# FPGA_Supply_Pins.net
KiCad netlist of a schematic drawn in Altium Designer
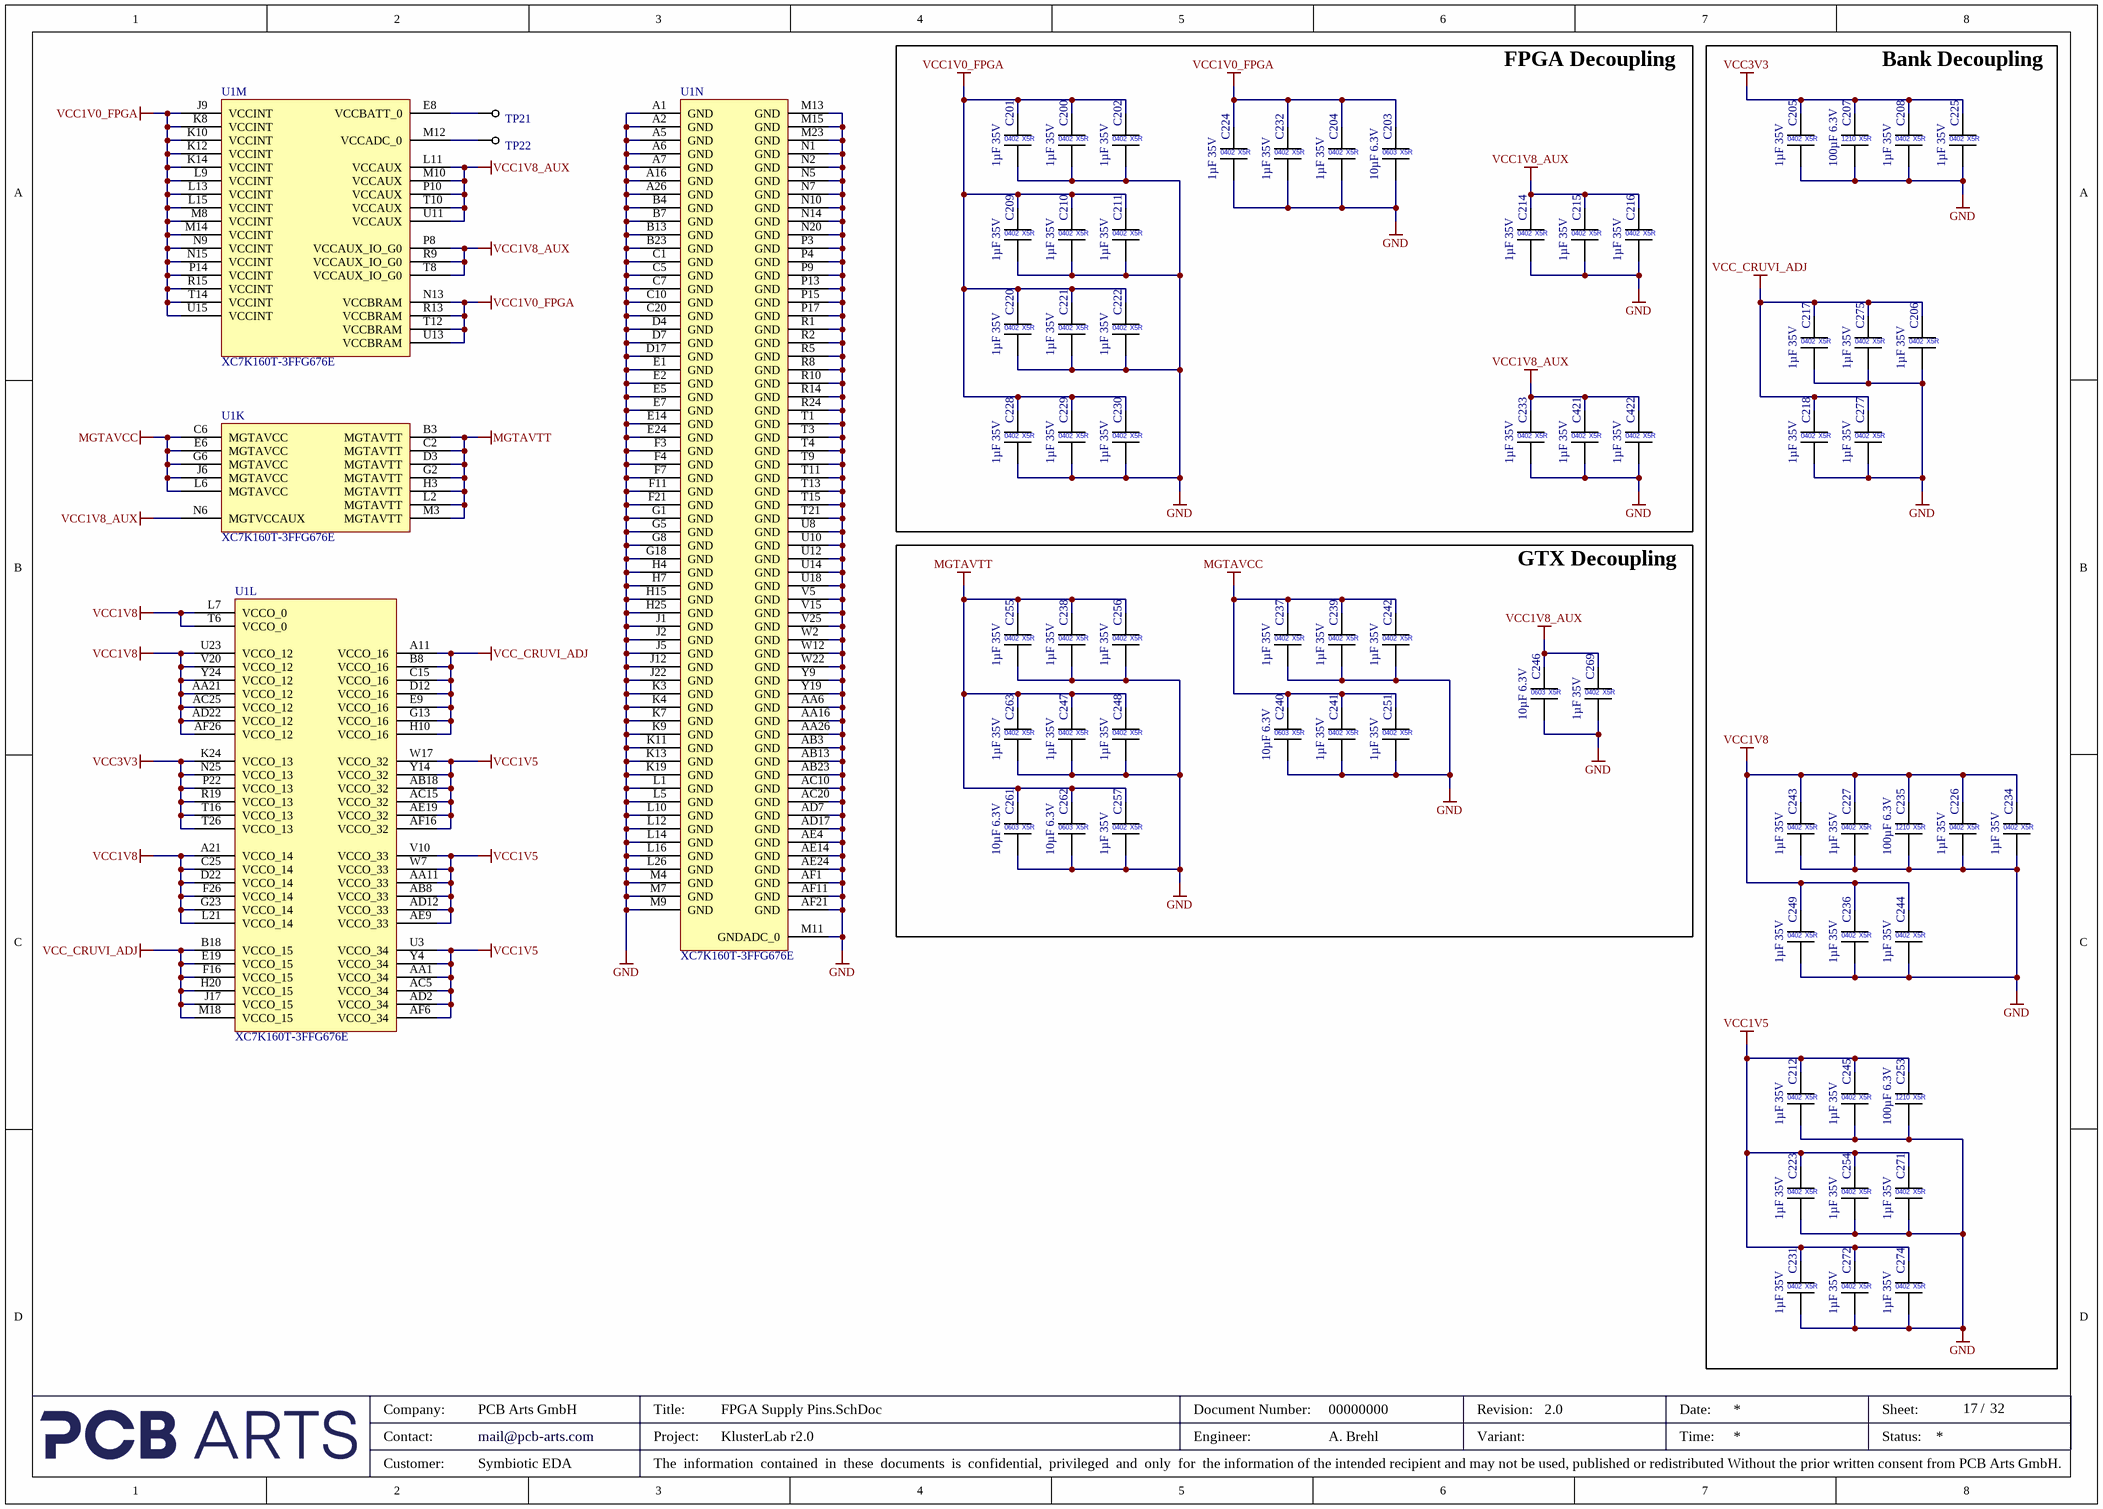
[diagram p0: FPGA Supply Pins.SchDoc]

(export (version "E")
  (design (tool "Eeschema 10.0.6"))
  (components
    (comp (ref "C200")
      (value "1µF 35V")
      (footprint "Cap:CAP_0402_L")
      (description "Multilayer Ceramic Capacitors MLCC - SMD/SMT 0402 35VDC")
      (libsource (lib "Cap") (part "CAP_0402_1µF_35V"))
    )
    (comp (ref "C201")
      (value "1µF 35V")
      (footprint "Cap:CAP_0402_L")
      (description "Multilayer Ceramic Capacitors MLCC - SMD/SMT 0402 35VDC")
      (libsource (lib "Cap") (part "CAP_0402_1µF_35V"))
    )
    (comp (ref "C202")
      (value "1µF 35V")
      (footprint "Cap:CAP_0402_L")
      (description "Multilayer Ceramic Capacitors MLCC - SMD/SMT 0402 35VDC")
      (libsource (lib "Cap") (part "CAP_0402_1µF_35V"))
    )
    (comp (ref "C203")
      (value "10µF 6.3V")
      (footprint "Cap:CAP_0603_L")
      (description "Multilayer Ceramic Capacitors MLCC - SMD/SMT 0603 6.3VDC")
      (libsource (lib "Cap") (part "CAP_0603_10µF_6.3V"))
    )
    (comp (ref "C204")
      (value "1µF 35V")
      (footprint "Cap:CAP_0402_L")
      (description "Multilayer Ceramic Capacitors MLCC - SMD/SMT 0402 35VDC")
      (libsource (lib "Cap") (part "CAP_0402_1µF_35V"))
    )
    (comp (ref "C205")
      (value "1µF 35V")
      (footprint "Cap:CAP_0402_L")
      (description "Multilayer Ceramic Capacitors MLCC - SMD/SMT 0402 35VDC")
      (libsource (lib "Cap") (part "CAP_0402_1µF_35V"))
    )
    (comp (ref "C206")
      (value "1µF 35V")
      (footprint "Cap:CAP_0402_L")
      (description "Multilayer Ceramic Capacitors MLCC - SMD/SMT 0402 35VDC")
      (libsource (lib "Cap") (part "CAP_0402_1µF_35V"))
    )
    (comp (ref "C207")
      (value "100µF 6.3V")
      (footprint "Cap:CAP_1210")
      (description "Multilayer Ceramic Capacitors MLCC - SMD/SMT 1210 6.3VDC")
      (libsource (lib "Cap") (part "CAP_1210_100µF_6.3V"))
    )
    (comp (ref "C208")
      (value "1µF 35V")
      (footprint "Cap:CAP_0402_L")
      (description "Multilayer Ceramic Capacitors MLCC - SMD/SMT 0402 35VDC")
      (libsource (lib "Cap") (part "CAP_0402_1µF_35V"))
    )
    (comp (ref "C209")
      (value "1µF 35V")
      (footprint "Cap:CAP_0402_L")
      (description "Multilayer Ceramic Capacitors MLCC - SMD/SMT 0402 35VDC")
      (libsource (lib "Cap") (part "CAP_0402_1µF_35V"))
    )
    (comp (ref "C210")
      (value "1µF 35V")
      (footprint "Cap:CAP_0402_L")
      (description "Multilayer Ceramic Capacitors MLCC - SMD/SMT 0402 35VDC")
      (libsource (lib "Cap") (part "CAP_0402_1µF_35V"))
    )
    (comp (ref "C211")
      (value "1µF 35V")
      (footprint "Cap:CAP_0402_L")
      (description "Multilayer Ceramic Capacitors MLCC - SMD/SMT 0402 35VDC")
      (libsource (lib "Cap") (part "CAP_0402_1µF_35V"))
    )
    (comp (ref "C212")
      (value "1µF 35V")
      (footprint "Cap:CAP_0402_L")
      (description "Multilayer Ceramic Capacitors MLCC - SMD/SMT 0402 35VDC")
      (libsource (lib "Cap") (part "CAP_0402_1µF_35V"))
    )
    (comp (ref "C214")
      (value "1µF 35V")
      (footprint "Cap:CAP_0402_L")
      (description "Multilayer Ceramic Capacitors MLCC - SMD/SMT 0402 35VDC")
      (libsource (lib "Cap") (part "CAP_0402_1µF_35V"))
    )
    (comp (ref "C215")
      (value "1µF 35V")
      (footprint "Cap:CAP_0402_L")
      (description "Multilayer Ceramic Capacitors MLCC - SMD/SMT 0402 35VDC")
      (libsource (lib "Cap") (part "CAP_0402_1µF_35V"))
    )
    (comp (ref "C216")
      (value "1µF 35V")
      (footprint "Cap:CAP_0402_L")
      (description "Multilayer Ceramic Capacitors MLCC - SMD/SMT 0402 35VDC")
      (libsource (lib "Cap") (part "CAP_0402_1µF_35V"))
    )
    (comp (ref "C217")
      (value "1µF 35V")
      (footprint "Cap:CAP_0402_L")
      (description "Multilayer Ceramic Capacitors MLCC - SMD/SMT 0402 35VDC")
      (libsource (lib "Cap") (part "CAP_0402_1µF_35V"))
    )
    (comp (ref "C218")
      (value "1µF 35V")
      (footprint "Cap:CAP_0402_L")
      (description "Multilayer Ceramic Capacitors MLCC - SMD/SMT 0402 35VDC")
      (libsource (lib "Cap") (part "CAP_0402_1µF_35V"))
    )
    (comp (ref "C220")
      (value "1µF 35V")
      (footprint "Cap:CAP_0402_L")
      (description "Multilayer Ceramic Capacitors MLCC - SMD/SMT 0402 35VDC")
      (libsource (lib "Cap") (part "CAP_0402_1µF_35V"))
    )
    (comp (ref "C221")
      (value "1µF 35V")
      (footprint "Cap:CAP_0402_L")
      (description "Multilayer Ceramic Capacitors MLCC - SMD/SMT 0402 35VDC")
      (libsource (lib "Cap") (part "CAP_0402_1µF_35V"))
    )
    (comp (ref "C222")
      (value "1µF 35V")
      (footprint "Cap:CAP_0402_L")
      (description "Multilayer Ceramic Capacitors MLCC - SMD/SMT 0402 35VDC")
      (libsource (lib "Cap") (part "CAP_0402_1µF_35V"))
    )
    (comp (ref "C223")
      (value "1µF 35V")
      (footprint "Cap:CAP_0402_L")
      (description "Multilayer Ceramic Capacitors MLCC - SMD/SMT 0402 35VDC")
      (libsource (lib "Cap") (part "CAP_0402_1µF_35V"))
    )
    (comp (ref "C224")
      (value "1µF 35V")
      (footprint "Cap:CAP_0402_L")
      (description "Multilayer Ceramic Capacitors MLCC - SMD/SMT 0402 35VDC")
      (libsource (lib "Cap") (part "CAP_0402_1µF_35V"))
    )
    (comp (ref "C225")
      (value "1µF 35V")
      (footprint "Cap:CAP_0402_L")
      (description "Multilayer Ceramic Capacitors MLCC - SMD/SMT 0402 35VDC")
      (libsource (lib "Cap") (part "CAP_0402_1µF_35V"))
    )
    (comp (ref "C226")
      (value "1µF 35V")
      (footprint "Cap:CAP_0402_L")
      (description "Multilayer Ceramic Capacitors MLCC - SMD/SMT 0402 35VDC")
      (libsource (lib "Cap") (part "CAP_0402_1µF_35V"))
    )
    (comp (ref "C227")
      (value "1µF 35V")
      (footprint "Cap:CAP_0402_L")
      (description "Multilayer Ceramic Capacitors MLCC - SMD/SMT 0402 35VDC")
      (libsource (lib "Cap") (part "CAP_0402_1µF_35V"))
    )
    (comp (ref "C228")
      (value "1µF 35V")
      (footprint "Cap:CAP_0402_L")
      (description "Multilayer Ceramic Capacitors MLCC - SMD/SMT 0402 35VDC")
      (libsource (lib "Cap") (part "CAP_0402_1µF_35V"))
    )
    (comp (ref "C229")
      (value "1µF 35V")
      (footprint "Cap:CAP_0402_L")
      (description "Multilayer Ceramic Capacitors MLCC - SMD/SMT 0402 35VDC")
      (libsource (lib "Cap") (part "CAP_0402_1µF_35V"))
    )
    (comp (ref "C230")
      (value "1µF 35V")
      (footprint "Cap:CAP_0402_L")
      (description "Multilayer Ceramic Capacitors MLCC - SMD/SMT 0402 35VDC")
      (libsource (lib "Cap") (part "CAP_0402_1µF_35V"))
    )
    (comp (ref "C231")
      (value "1µF 35V")
      (footprint "Cap:CAP_0402_L")
      (description "Multilayer Ceramic Capacitors MLCC - SMD/SMT 0402 35VDC")
      (libsource (lib "Cap") (part "CAP_0402_1µF_35V"))
    )
    (comp (ref "C232")
      (value "1µF 35V")
      (footprint "Cap:CAP_0402_L")
      (description "Multilayer Ceramic Capacitors MLCC - SMD/SMT 0402 35VDC")
      (libsource (lib "Cap") (part "CAP_0402_1µF_35V"))
    )
    (comp (ref "C233")
      (value "1µF 35V")
      (footprint "Cap:CAP_0402_L")
      (description "Multilayer Ceramic Capacitors MLCC - SMD/SMT 0402 35VDC")
      (libsource (lib "Cap") (part "CAP_0402_1µF_35V"))
    )
    (comp (ref "C234")
      (value "1µF 35V")
      (footprint "Cap:CAP_0402_L")
      (description "Multilayer Ceramic Capacitors MLCC - SMD/SMT 0402 35VDC")
      (libsource (lib "Cap") (part "CAP_0402_1µF_35V"))
    )
    (comp (ref "C235")
      (value "100µF 6.3V")
      (footprint "Cap:CAP_1210")
      (description "Multilayer Ceramic Capacitors MLCC - SMD/SMT 1210 6.3VDC")
      (libsource (lib "Cap") (part "CAP_1210_100µF_6.3V"))
    )
    (comp (ref "C236")
      (value "1µF 35V")
      (footprint "Cap:CAP_0402_L")
      (description "Multilayer Ceramic Capacitors MLCC - SMD/SMT 0402 35VDC")
      (libsource (lib "Cap") (part "CAP_0402_1µF_35V"))
    )
    (comp (ref "C237")
      (value "1µF 35V")
      (footprint "Cap:CAP_0402_L")
      (description "Multilayer Ceramic Capacitors MLCC - SMD/SMT 0402 35VDC")
      (libsource (lib "Cap") (part "CAP_0402_1µF_35V"))
    )
    (comp (ref "C238")
      (value "1µF 35V")
      (footprint "Cap:CAP_0402_L")
      (description "Multilayer Ceramic Capacitors MLCC - SMD/SMT 0402 35VDC")
      (libsource (lib "Cap") (part "CAP_0402_1µF_35V"))
    )
    (comp (ref "C239")
      (value "1µF 35V")
      (footprint "Cap:CAP_0402_L")
      (description "Multilayer Ceramic Capacitors MLCC - SMD/SMT 0402 35VDC")
      (libsource (lib "Cap") (part "CAP_0402_1µF_35V"))
    )
    (comp (ref "C240")
      (value "10µF 6.3V")
      (footprint "Cap:CAP_0603_L")
      (description "Multilayer Ceramic Capacitors MLCC - SMD/SMT 0603 6.3VDC")
      (libsource (lib "Cap") (part "CAP_0603_10µF_6.3V"))
    )
    (comp (ref "C241")
      (value "1µF 35V")
      (footprint "Cap:CAP_0402_L")
      (description "Multilayer Ceramic Capacitors MLCC - SMD/SMT 0402 35VDC")
      (libsource (lib "Cap") (part "CAP_0402_1µF_35V"))
    )
    (comp (ref "C242")
      (value "1µF 35V")
      (footprint "Cap:CAP_0402_L")
      (description "Multilayer Ceramic Capacitors MLCC - SMD/SMT 0402 35VDC")
      (libsource (lib "Cap") (part "CAP_0402_1µF_35V"))
    )
    (comp (ref "C243")
      (value "1µF 35V")
      (footprint "Cap:CAP_0402_L")
      (description "Multilayer Ceramic Capacitors MLCC - SMD/SMT 0402 35VDC")
      (libsource (lib "Cap") (part "CAP_0402_1µF_35V"))
    )
    (comp (ref "C244")
      (value "1µF 35V")
      (footprint "Cap:CAP_0402_L")
      (description "Multilayer Ceramic Capacitors MLCC - SMD/SMT 0402 35VDC")
      (libsource (lib "Cap") (part "CAP_0402_1µF_35V"))
    )
    (comp (ref "C245")
      (value "1µF 35V")
      (footprint "Cap:CAP_0402_L")
      (description "Multilayer Ceramic Capacitors MLCC - SMD/SMT 0402 35VDC")
      (libsource (lib "Cap") (part "CAP_0402_1µF_35V"))
    )
    (comp (ref "C246")
      (value "10µF 6.3V")
      (footprint "Cap:CAP_0603_L")
      (description "Multilayer Ceramic Capacitors MLCC - SMD/SMT 0603 6.3VDC")
      (libsource (lib "Cap") (part "CAP_0603_10µF_6.3V"))
    )
    (comp (ref "C247")
      (value "1µF 35V")
      (footprint "Cap:CAP_0402_L")
      (description "Multilayer Ceramic Capacitors MLCC - SMD/SMT 0402 35VDC")
      (libsource (lib "Cap") (part "CAP_0402_1µF_35V"))
    )
    (comp (ref "C248")
      (value "1µF 35V")
      (footprint "Cap:CAP_0402_L")
      (description "Multilayer Ceramic Capacitors MLCC - SMD/SMT 0402 35VDC")
      (libsource (lib "Cap") (part "CAP_0402_1µF_35V"))
    )
    (comp (ref "C249")
      (value "1µF 35V")
      (footprint "Cap:CAP_0402_L")
      (description "Multilayer Ceramic Capacitors MLCC - SMD/SMT 0402 35VDC")
      (libsource (lib "Cap") (part "CAP_0402_1µF_35V"))
    )
    (comp (ref "C251")
      (value "1µF 35V")
      (footprint "Cap:CAP_0402_L")
      (description "Multilayer Ceramic Capacitors MLCC - SMD/SMT 0402 35VDC")
      (libsource (lib "Cap") (part "CAP_0402_1µF_35V"))
    )
    (comp (ref "C253")
      (value "100µF 6.3V")
      (footprint "Cap:CAP_1210")
      (description "Multilayer Ceramic Capacitors MLCC - SMD/SMT 1210 6.3VDC")
      (libsource (lib "Cap") (part "CAP_1210_100µF_6.3V"))
    )
    (comp (ref "C254")
      (value "1µF 35V")
      (footprint "Cap:CAP_0402_L")
      (description "Multilayer Ceramic Capacitors MLCC - SMD/SMT 0402 35VDC")
      (libsource (lib "Cap") (part "CAP_0402_1µF_35V"))
    )
    (comp (ref "C255")
      (value "1µF 35V")
      (footprint "Cap:CAP_0402_L")
      (description "Multilayer Ceramic Capacitors MLCC - SMD/SMT 0402 35VDC")
      (libsource (lib "Cap") (part "CAP_0402_1µF_35V"))
    )
    (comp (ref "C256")
      (value "1µF 35V")
      (footprint "Cap:CAP_0402_L")
      (description "Multilayer Ceramic Capacitors MLCC - SMD/SMT 0402 35VDC")
      (libsource (lib "Cap") (part "CAP_0402_1µF_35V"))
    )
    (comp (ref "C257")
      (value "1µF 35V")
      (footprint "Cap:CAP_0402_L")
      (description "Multilayer Ceramic Capacitors MLCC - SMD/SMT 0402 35VDC")
      (libsource (lib "Cap") (part "CAP_0402_1µF_35V"))
    )
    (comp (ref "C261")
      (value "10µF 6.3V")
      (footprint "Cap:CAP_0603_L")
      (description "Multilayer Ceramic Capacitors MLCC - SMD/SMT 0603 6.3VDC")
      (libsource (lib "Cap") (part "CAP_0603_10µF_6.3V"))
    )
    (comp (ref "C262")
      (value "10µF 6.3V")
      (footprint "Cap:CAP_0603_L")
      (description "Multilayer Ceramic Capacitors MLCC - SMD/SMT 0603 6.3VDC")
      (libsource (lib "Cap") (part "CAP_0603_10µF_6.3V"))
    )
    (comp (ref "C263")
      (value "1µF 35V")
      (footprint "Cap:CAP_0402_L")
      (description "Multilayer Ceramic Capacitors MLCC - SMD/SMT 0402 35VDC")
      (libsource (lib "Cap") (part "CAP_0402_1µF_35V"))
    )
    (comp (ref "C269")
      (value "1µF 35V")
      (footprint "Cap:CAP_0402_L")
      (description "Multilayer Ceramic Capacitors MLCC - SMD/SMT 0402 35VDC")
      (libsource (lib "Cap") (part "CAP_0402_1µF_35V"))
    )
    (comp (ref "C271")
      (value "1µF 35V")
      (footprint "Cap:CAP_0402_L")
      (description "Multilayer Ceramic Capacitors MLCC - SMD/SMT 0402 35VDC")
      (libsource (lib "Cap") (part "CAP_0402_1µF_35V"))
    )
    (comp (ref "C272")
      (value "1µF 35V")
      (footprint "Cap:CAP_0402_L")
      (description "Multilayer Ceramic Capacitors MLCC - SMD/SMT 0402 35VDC")
      (libsource (lib "Cap") (part "CAP_0402_1µF_35V"))
    )
    (comp (ref "C274")
      (value "1µF 35V")
      (footprint "Cap:CAP_0402_L")
      (description "Multilayer Ceramic Capacitors MLCC - SMD/SMT 0402 35VDC")
      (libsource (lib "Cap") (part "CAP_0402_1µF_35V"))
    )
    (comp (ref "C275")
      (value "1µF 35V")
      (footprint "Cap:CAP_0402_L")
      (description "Multilayer Ceramic Capacitors MLCC - SMD/SMT 0402 35VDC")
      (libsource (lib "Cap") (part "CAP_0402_1µF_35V"))
    )
    (comp (ref "C277")
      (value "1µF 35V")
      (footprint "Cap:CAP_0402_L")
      (description "Multilayer Ceramic Capacitors MLCC - SMD/SMT 0402 35VDC")
      (libsource (lib "Cap") (part "CAP_0402_1µF_35V"))
    )
    (comp (ref "C421")
      (value "1µF 35V")
      (footprint "Cap:CAP_0402_L")
      (description "Multilayer Ceramic Capacitors MLCC - SMD/SMT 0402 35VDC")
      (libsource (lib "Cap") (part "CAP_0402_1µF_35V"))
    )
    (comp (ref "C422")
      (value "1µF 35V")
      (footprint "Cap:CAP_0402_L")
      (description "Multilayer Ceramic Capacitors MLCC - SMD/SMT 0402 35VDC")
      (libsource (lib "Cap") (part "CAP_0402_1µF_35V"))
    )
    (comp (ref "TP21")
      (value "Testpoint")
      (footprint "Electro_mech:Testpoint 0.8mm")
      (description "Testpoint 0.8mm")
      (libsource (lib "Electro_Mech") (part "Testpoint 0.8mm"))
    )
    (comp (ref "TP22")
      (value "Testpoint")
      (footprint "Electro_mech:Testpoint 0.8mm")
      (description "Testpoint 0.8mm")
      (libsource (lib "Electro_Mech") (part "Testpoint 0.8mm"))
    )
    (comp (ref "U1")
      (value "XC7K160T-3FFG676E")
      (footprint "Digital:BGA100P2700X2700X317-676N")
      (description "Kintex-7 FPGA, 400 User I/Os, 8 GTX, 676-Ball BGA, Speed Grade 3, Extended Grade, Pb-Free")
      (libsource (lib "Digital") (part "XC7K160T-3FFG676E_Kintex-7 FPGA, 400 User I/Os, 8 GTX, FFG676"))
    )
  )
  (nets
    (net (code "1") (name "GND") (class "Default")
      (node (ref "C200") (pin "2") (pinfunction "2_2") (pintype "passive"))
      (node (ref "C201") (pin "2") (pinfunction "2_2") (pintype "passive"))
      (node (ref "C202") (pin "2") (pinfunction "2_2") (pintype "passive"))
      (node (ref "C203") (pin "2") (pinfunction "2_2") (pintype "passive"))
      (node (ref "C204") (pin "2") (pinfunction "2_2") (pintype "passive"))
      (node (ref "C205") (pin "2") (pinfunction "2_2") (pintype "passive"))
      (node (ref "C206") (pin "2") (pinfunction "2_2") (pintype "passive"))
      (node (ref "C207") (pin "2") (pinfunction "2_2") (pintype "passive"))
      (node (ref "C208") (pin "2") (pinfunction "2_2") (pintype "passive"))
      (node (ref "C209") (pin "2") (pinfunction "2_2") (pintype "passive"))
      (node (ref "C210") (pin "2") (pinfunction "2_2") (pintype "passive"))
      (node (ref "C211") (pin "2") (pinfunction "2_2") (pintype "passive"))
      (node (ref "C212") (pin "2") (pinfunction "2_2") (pintype "passive"))
      (node (ref "C214") (pin "2") (pinfunction "2_2") (pintype "passive"))
      (node (ref "C215") (pin "2") (pinfunction "2_2") (pintype "passive"))
      (node (ref "C216") (pin "2") (pinfunction "2_2") (pintype "passive"))
      (node (ref "C217") (pin "2") (pinfunction "2_2") (pintype "passive"))
      (node (ref "C218") (pin "2") (pinfunction "2_2") (pintype "passive"))
      (node (ref "C220") (pin "2") (pinfunction "2_2") (pintype "passive"))
      (node (ref "C221") (pin "2") (pinfunction "2_2") (pintype "passive"))
      (node (ref "C222") (pin "2") (pinfunction "2_2") (pintype "passive"))
      (node (ref "C223") (pin "2") (pinfunction "2_2") (pintype "passive"))
      (node (ref "C224") (pin "2") (pinfunction "2_2") (pintype "passive"))
      (node (ref "C225") (pin "2") (pinfunction "2_2") (pintype "passive"))
      (node (ref "C226") (pin "2") (pinfunction "2_2") (pintype "passive"))
      (node (ref "C227") (pin "2") (pinfunction "2_2") (pintype "passive"))
      (node (ref "C228") (pin "2") (pinfunction "2_2") (pintype "passive"))
      (node (ref "C229") (pin "2") (pinfunction "2_2") (pintype "passive"))
      (node (ref "C230") (pin "2") (pinfunction "2_2") (pintype "passive"))
      (node (ref "C231") (pin "2") (pinfunction "2_2") (pintype "passive"))
      (node (ref "C232") (pin "2") (pinfunction "2_2") (pintype "passive"))
      (node (ref "C233") (pin "2") (pinfunction "2_2") (pintype "passive"))
      (node (ref "C234") (pin "2") (pinfunction "2_2") (pintype "passive"))
      (node (ref "C235") (pin "2") (pinfunction "2_2") (pintype "passive"))
      (node (ref "C236") (pin "2") (pinfunction "2_2") (pintype "passive"))
      (node (ref "C237") (pin "2") (pinfunction "2_2") (pintype "passive"))
      (node (ref "C238") (pin "2") (pinfunction "2_2") (pintype "passive"))
      (node (ref "C239") (pin "2") (pinfunction "2_2") (pintype "passive"))
      (node (ref "C240") (pin "2") (pinfunction "2_2") (pintype "passive"))
      (node (ref "C241") (pin "2") (pinfunction "2_2") (pintype "passive"))
      (node (ref "C242") (pin "2") (pinfunction "2_2") (pintype "passive"))
      (node (ref "C243") (pin "2") (pinfunction "2_2") (pintype "passive"))
      (node (ref "C244") (pin "2") (pinfunction "2_2") (pintype "passive"))
      (node (ref "C245") (pin "2") (pinfunction "2_2") (pintype "passive"))
      (node (ref "C246") (pin "2") (pinfunction "2_2") (pintype "passive"))
      (node (ref "C247") (pin "2") (pinfunction "2_2") (pintype "passive"))
      (node (ref "C248") (pin "2") (pinfunction "2_2") (pintype "passive"))
      (node (ref "C249") (pin "2") (pinfunction "2_2") (pintype "passive"))
      (node (ref "C251") (pin "2") (pinfunction "2_2") (pintype "passive"))
      (node (ref "C253") (pin "2") (pinfunction "2_2") (pintype "passive"))
      (node (ref "C254") (pin "2") (pinfunction "2_2") (pintype "passive"))
      (node (ref "C255") (pin "2") (pinfunction "2_2") (pintype "passive"))
      (node (ref "C256") (pin "2") (pinfunction "2_2") (pintype "passive"))
      (node (ref "C257") (pin "2") (pinfunction "2_2") (pintype "passive"))
      (node (ref "C261") (pin "2") (pinfunction "2_2") (pintype "passive"))
      (node (ref "C262") (pin "2") (pinfunction "2_2") (pintype "passive"))
      (node (ref "C263") (pin "2") (pinfunction "2_2") (pintype "passive"))
      (node (ref "C269") (pin "2") (pinfunction "2_2") (pintype "passive"))
      (node (ref "C271") (pin "2") (pinfunction "2_2") (pintype "passive"))
      (node (ref "C272") (pin "2") (pinfunction "2_2") (pintype "passive"))
      (node (ref "C274") (pin "2") (pinfunction "2_2") (pintype "passive"))
      (node (ref "C275") (pin "2") (pinfunction "2_2") (pintype "passive"))
      (node (ref "C277") (pin "2") (pinfunction "2_2") (pintype "passive"))
      (node (ref "C421") (pin "2") (pinfunction "2_2") (pintype "passive"))
      (node (ref "C422") (pin "2") (pinfunction "2_2") (pintype "passive"))
      (node (ref "U1") (pin "A1") (pinfunction "GND_A1") (pintype "power_in"))
      (node (ref "U1") (pin "A16") (pinfunction "GND_A16") (pintype "power_in"))
      (node (ref "U1") (pin "A2") (pinfunction "GND_A2") (pintype "power_in"))
      (node (ref "U1") (pin "A26") (pinfunction "GND_A26") (pintype "power_in"))
      (node (ref "U1") (pin "A5") (pinfunction "GND_A5") (pintype "power_in"))
      (node (ref "U1") (pin "A6") (pinfunction "GND_A6") (pintype "power_in"))
      (node (ref "U1") (pin "A7") (pinfunction "GND_A7") (pintype "power_in"))
      (node (ref "U1") (pin "AA16") (pinfunction "GND_AA16") (pintype "power_in"))
      (node (ref "U1") (pin "AA26") (pinfunction "GND_AA26") (pintype "power_in"))
      (node (ref "U1") (pin "AA6") (pinfunction "GND_AA6") (pintype "power_in"))
      (node (ref "U1") (pin "AB13") (pinfunction "GND_AB13") (pintype "power_in"))
      (node (ref "U1") (pin "AB23") (pinfunction "GND_AB23") (pintype "power_in"))
      (node (ref "U1") (pin "AB3") (pinfunction "GND_AB3") (pintype "power_in"))
      (node (ref "U1") (pin "AC10") (pinfunction "GND_AC10") (pintype "power_in"))
      (node (ref "U1") (pin "AC20") (pinfunction "GND_AC20") (pintype "power_in"))
      (node (ref "U1") (pin "AD17") (pinfunction "GND_AD17") (pintype "power_in"))
      (node (ref "U1") (pin "AD7") (pinfunction "GND_AD7") (pintype "power_in"))
      (node (ref "U1") (pin "AE14") (pinfunction "GND_AE14") (pintype "power_in"))
      (node (ref "U1") (pin "AE24") (pinfunction "GND_AE24") (pintype "power_in"))
      (node (ref "U1") (pin "AE4") (pinfunction "GND_AE4") (pintype "power_in"))
      (node (ref "U1") (pin "AF1") (pinfunction "GND_AF1") (pintype "power_in"))
      (node (ref "U1") (pin "AF11") (pinfunction "GND_AF11") (pintype "power_in"))
      (node (ref "U1") (pin "AF21") (pinfunction "GND_AF21") (pintype "power_in"))
      (node (ref "U1") (pin "B13") (pinfunction "GND_B13") (pintype "power_in"))
      (node (ref "U1") (pin "B23") (pinfunction "GND_B23") (pintype "power_in"))
      (node (ref "U1") (pin "B4") (pinfunction "GND_B4") (pintype "power_in"))
      (node (ref "U1") (pin "B7") (pinfunction "GND_B7") (pintype "power_in"))
      (node (ref "U1") (pin "C1") (pinfunction "GND_C1") (pintype "power_in"))
      (node (ref "U1") (pin "C10") (pinfunction "GND_C10") (pintype "power_in"))
      (node (ref "U1") (pin "C20") (pinfunction "GND_C20") (pintype "power_in"))
      (node (ref "U1") (pin "C5") (pinfunction "GND_C5") (pintype "power_in"))
      (node (ref "U1") (pin "C7") (pinfunction "GND_C7") (pintype "power_in"))
      (node (ref "U1") (pin "D17") (pinfunction "GND_D17") (pintype "power_in"))
      (node (ref "U1") (pin "D4") (pinfunction "GND_D4") (pintype "power_in"))
      (node (ref "U1") (pin "D7") (pinfunction "GND_D7") (pintype "power_in"))
      (node (ref "U1") (pin "E1") (pinfunction "GND_E1") (pintype "power_in"))
      (node (ref "U1") (pin "E14") (pinfunction "GND_E14") (pintype "power_in"))
      (node (ref "U1") (pin "E2") (pinfunction "GND_E2") (pintype "power_in"))
      (node (ref "U1") (pin "E24") (pinfunction "GND_E24") (pintype "power_in"))
      (node (ref "U1") (pin "E5") (pinfunction "GND_E5") (pintype "power_in"))
      (node (ref "U1") (pin "E7") (pinfunction "GND_E7") (pintype "power_in"))
      (node (ref "U1") (pin "F11") (pinfunction "GND_F11") (pintype "power_in"))
      (node (ref "U1") (pin "F21") (pinfunction "GND_F21") (pintype "power_in"))
      (node (ref "U1") (pin "F3") (pinfunction "GND_F3") (pintype "power_in"))
      (node (ref "U1") (pin "F4") (pinfunction "GND_F4") (pintype "power_in"))
      (node (ref "U1") (pin "F7") (pinfunction "GND_F7") (pintype "power_in"))
      (node (ref "U1") (pin "G1") (pinfunction "GND_G1") (pintype "power_in"))
      (node (ref "U1") (pin "G18") (pinfunction "GND_G18") (pintype "power_in"))
      (node (ref "U1") (pin "G5") (pinfunction "GND_G5") (pintype "power_in"))
      (node (ref "U1") (pin "G8") (pinfunction "GND_G8") (pintype "power_in"))
      (node (ref "U1") (pin "H15") (pinfunction "GND_H15") (pintype "power_in"))
      (node (ref "U1") (pin "H25") (pinfunction "GND_H25") (pintype "power_in"))
      (node (ref "U1") (pin "H4") (pinfunction "GND_H4") (pintype "power_in"))
      (node (ref "U1") (pin "H7") (pinfunction "GND_H7") (pintype "power_in"))
      (node (ref "U1") (pin "J1") (pinfunction "GND_J1") (pintype "power_in"))
      (node (ref "U1") (pin "J12") (pinfunction "GND_J12") (pintype "power_in"))
      (node (ref "U1") (pin "J2") (pinfunction "GND_J2") (pintype "power_in"))
      (node (ref "U1") (pin "J22") (pinfunction "GND_J22") (pintype "power_in"))
      (node (ref "U1") (pin "J5") (pinfunction "GND_J5") (pintype "power_in"))
      (node (ref "U1") (pin "K11") (pinfunction "GND_K11") (pintype "power_in"))
      (node (ref "U1") (pin "K13") (pinfunction "GND_K13") (pintype "power_in"))
      (node (ref "U1") (pin "K19") (pinfunction "GND_K19") (pintype "power_in"))
      (node (ref "U1") (pin "K3") (pinfunction "GND_K3") (pintype "power_in"))
      (node (ref "U1") (pin "K4") (pinfunction "GND_K4") (pintype "power_in"))
      (node (ref "U1") (pin "K7") (pinfunction "GND_K7") (pintype "power_in"))
      (node (ref "U1") (pin "K9") (pinfunction "GND_K9") (pintype "power_in"))
      (node (ref "U1") (pin "L1") (pinfunction "GND_L1") (pintype "power_in"))
      (node (ref "U1") (pin "L10") (pinfunction "GND_L10") (pintype "power_in"))
      (node (ref "U1") (pin "L12") (pinfunction "GND_L12") (pintype "power_in"))
      (node (ref "U1") (pin "L14") (pinfunction "GND_L14") (pintype "power_in"))
      (node (ref "U1") (pin "L16") (pinfunction "GND_L16") (pintype "power_in"))
      (node (ref "U1") (pin "L26") (pinfunction "GND_L26") (pintype "power_in"))
      (node (ref "U1") (pin "L5") (pinfunction "GND_L5") (pintype "power_in"))
      (node (ref "U1") (pin "M11") (pinfunction "GNDADC_0_M11") (pintype "power_in"))
      (node (ref "U1") (pin "M13") (pinfunction "GND_M13") (pintype "power_in"))
      (node (ref "U1") (pin "M15") (pinfunction "GND_M15") (pintype "power_in"))
      (node (ref "U1") (pin "M23") (pinfunction "GND_M23") (pintype "power_in"))
      (node (ref "U1") (pin "M4") (pinfunction "GND_M4") (pintype "power_in"))
      (node (ref "U1") (pin "M7") (pinfunction "GND_M7") (pintype "power_in"))
      (node (ref "U1") (pin "M9") (pinfunction "GND_M9") (pintype "power_in"))
      (node (ref "U1") (pin "N1") (pinfunction "GND_N1") (pintype "power_in"))
      (node (ref "U1") (pin "N10") (pinfunction "GND_N10") (pintype "power_in"))
      (node (ref "U1") (pin "N14") (pinfunction "GND_N14") (pintype "power_in"))
      (node (ref "U1") (pin "N2") (pinfunction "GND_N2") (pintype "power_in"))
      (node (ref "U1") (pin "N20") (pinfunction "GND_N20") (pintype "power_in"))
      (node (ref "U1") (pin "N5") (pinfunction "GND_N5") (pintype "power_in"))
      (node (ref "U1") (pin "N7") (pinfunction "GND_N7") (pintype "power_in"))
      (node (ref "U1") (pin "P13") (pinfunction "GND_P13") (pintype "power_in"))
      (node (ref "U1") (pin "P15") (pinfunction "GND_P15") (pintype "power_in"))
      (node (ref "U1") (pin "P17") (pinfunction "GND_P17") (pintype "power_in"))
      (node (ref "U1") (pin "P3") (pinfunction "GND_P3") (pintype "power_in"))
      (node (ref "U1") (pin "P4") (pinfunction "GND_P4") (pintype "power_in"))
      (node (ref "U1") (pin "P9") (pinfunction "GND_P9") (pintype "power_in"))
      (node (ref "U1") (pin "R1") (pinfunction "GND_R1") (pintype "power_in"))
      (node (ref "U1") (pin "R10") (pinfunction "GND_R10") (pintype "power_in"))
      (node (ref "U1") (pin "R14") (pinfunction "GND_R14") (pintype "power_in"))
      (node (ref "U1") (pin "R2") (pinfunction "GND_R2") (pintype "power_in"))
      (node (ref "U1") (pin "R24") (pinfunction "GND_R24") (pintype "power_in"))
      (node (ref "U1") (pin "R5") (pinfunction "GND_R5") (pintype "power_in"))
      (node (ref "U1") (pin "R8") (pinfunction "GND_R8") (pintype "power_in"))
      (node (ref "U1") (pin "T1") (pinfunction "GND_T1") (pintype "power_in"))
      (node (ref "U1") (pin "T11") (pinfunction "GND_T11") (pintype "power_in"))
      (node (ref "U1") (pin "T13") (pinfunction "GND_T13") (pintype "power_in"))
      (node (ref "U1") (pin "T15") (pinfunction "GND_T15") (pintype "power_in"))
      (node (ref "U1") (pin "T21") (pinfunction "GND_T21") (pintype "power_in"))
      (node (ref "U1") (pin "T3") (pinfunction "GND_T3") (pintype "power_in"))
      (node (ref "U1") (pin "T4") (pinfunction "GND_T4") (pintype "power_in"))
      (node (ref "U1") (pin "T9") (pinfunction "GND_T9") (pintype "power_in"))
      (node (ref "U1") (pin "U10") (pinfunction "GND_U10") (pintype "power_in"))
      (node (ref "U1") (pin "U12") (pinfunction "GND_U12") (pintype "power_in"))
      (node (ref "U1") (pin "U14") (pinfunction "GND_U14") (pintype "power_in"))
      (node (ref "U1") (pin "U18") (pinfunction "GND_U18") (pintype "power_in"))
      (node (ref "U1") (pin "U8") (pinfunction "GND_U8") (pintype "power_in"))
      (node (ref "U1") (pin "V15") (pinfunction "GND_V15") (pintype "power_in"))
      (node (ref "U1") (pin "V25") (pinfunction "GND_V25") (pintype "power_in"))
      (node (ref "U1") (pin "V5") (pinfunction "GND_V5") (pintype "power_in"))
      (node (ref "U1") (pin "W12") (pinfunction "GND_W12") (pintype "power_in"))
      (node (ref "U1") (pin "W2") (pinfunction "GND_W2") (pintype "power_in"))
      (node (ref "U1") (pin "W22") (pinfunction "GND_W22") (pintype "power_in"))
      (node (ref "U1") (pin "Y19") (pinfunction "GND_Y19") (pintype "power_in"))
      (node (ref "U1") (pin "Y9") (pinfunction "GND_Y9") (pintype "power_in"))
    )
    (net (code "2") (name "MGTAVCC") (class "Default")
      (node (ref "C237") (pin "1") (pinfunction "1_1") (pintype "passive"))
      (node (ref "C239") (pin "1") (pinfunction "1_1") (pintype "passive"))
      (node (ref "C240") (pin "1") (pinfunction "1_1") (pintype "passive"))
      (node (ref "C241") (pin "1") (pinfunction "1_1") (pintype "passive"))
      (node (ref "C242") (pin "1") (pinfunction "1_1") (pintype "passive"))
      (node (ref "C251") (pin "1") (pinfunction "1_1") (pintype "passive"))
      (node (ref "U1") (pin "C6") (pinfunction "MGTAVCC_C6") (pintype "power_in"))
      (node (ref "U1") (pin "E6") (pinfunction "MGTAVCC_E6") (pintype "power_in"))
      (node (ref "U1") (pin "G6") (pinfunction "MGTAVCC_G6") (pintype "power_in"))
      (node (ref "U1") (pin "J6") (pinfunction "MGTAVCC_J6") (pintype "power_in"))
      (node (ref "U1") (pin "L6") (pinfunction "MGTAVCC_L6") (pintype "power_in"))
    )
    (net (code "3") (name "MGTAVTT") (class "Default")
      (node (ref "C238") (pin "1") (pinfunction "1_1") (pintype "passive"))
      (node (ref "C247") (pin "1") (pinfunction "1_1") (pintype "passive"))
      (node (ref "C248") (pin "1") (pinfunction "1_1") (pintype "passive"))
      (node (ref "C255") (pin "1") (pinfunction "1_1") (pintype "passive"))
      (node (ref "C256") (pin "1") (pinfunction "1_1") (pintype "passive"))
      (node (ref "C257") (pin "1") (pinfunction "1_1") (pintype "passive"))
      (node (ref "C261") (pin "1") (pinfunction "1_1") (pintype "passive"))
      (node (ref "C262") (pin "1") (pinfunction "1_1") (pintype "passive"))
      (node (ref "C263") (pin "1") (pinfunction "1_1") (pintype "passive"))
      (node (ref "U1") (pin "B3") (pinfunction "MGTAVTT_B3") (pintype "power_in"))
      (node (ref "U1") (pin "C2") (pinfunction "MGTAVTT_C2") (pintype "power_in"))
      (node (ref "U1") (pin "D3") (pinfunction "MGTAVTT_D3") (pintype "power_in"))
      (node (ref "U1") (pin "G2") (pinfunction "MGTAVTT_G2") (pintype "power_in"))
      (node (ref "U1") (pin "H3") (pinfunction "MGTAVTT_H3") (pintype "power_in"))
      (node (ref "U1") (pin "L2") (pinfunction "MGTAVTT_L2") (pintype "power_in"))
      (node (ref "U1") (pin "M3") (pinfunction "MGTAVTT_M3") (pintype "power_in"))
    )
    (net (code "4") (name "Net-(TP21-GND)") (class "Default")
      (node (ref "TP21") (pin "1") (pinfunction "GND_1") (pintype "passive"))
      (node (ref "U1") (pin "E8") (pinfunction "VCCBATT_0_E8") (pintype "power_in"))
    )
    (net (code "5") (name "Net-(TP22-GND)") (class "Default")
      (node (ref "TP22") (pin "1") (pinfunction "GND_1") (pintype "passive"))
      (node (ref "U1") (pin "M12") (pinfunction "VCCADC_0_M12") (pintype "power_in"))
    )
    (net (code "6") (name "VCC1V0_FPGA") (class "Default")
      (node (ref "C200") (pin "1") (pinfunction "1_1") (pintype "passive"))
      (node (ref "C201") (pin "1") (pinfunction "1_1") (pintype "passive"))
      (node (ref "C202") (pin "1") (pinfunction "1_1") (pintype "passive"))
      (node (ref "C203") (pin "1") (pinfunction "1_1") (pintype "passive"))
      (node (ref "C204") (pin "1") (pinfunction "1_1") (pintype "passive"))
      (node (ref "C209") (pin "1") (pinfunction "1_1") (pintype "passive"))
      (node (ref "C210") (pin "1") (pinfunction "1_1") (pintype "passive"))
      (node (ref "C211") (pin "1") (pinfunction "1_1") (pintype "passive"))
      (node (ref "C220") (pin "1") (pinfunction "1_1") (pintype "passive"))
      (node (ref "C221") (pin "1") (pinfunction "1_1") (pintype "passive"))
      (node (ref "C222") (pin "1") (pinfunction "1_1") (pintype "passive"))
      (node (ref "C224") (pin "1") (pinfunction "1_1") (pintype "passive"))
      (node (ref "C228") (pin "1") (pinfunction "1_1") (pintype "passive"))
      (node (ref "C229") (pin "1") (pinfunction "1_1") (pintype "passive"))
      (node (ref "C230") (pin "1") (pinfunction "1_1") (pintype "passive"))
      (node (ref "C232") (pin "1") (pinfunction "1_1") (pintype "passive"))
      (node (ref "U1") (pin "J9") (pinfunction "VCCINT_J9") (pintype "power_in"))
      (node (ref "U1") (pin "K10") (pinfunction "VCCINT_K10") (pintype "power_in"))
      (node (ref "U1") (pin "K12") (pinfunction "VCCINT_K12") (pintype "power_in"))
      (node (ref "U1") (pin "K14") (pinfunction "VCCINT_K14") (pintype "power_in"))
      (node (ref "U1") (pin "K8") (pinfunction "VCCINT_K8") (pintype "power_in"))
      (node (ref "U1") (pin "L13") (pinfunction "VCCINT_L13") (pintype "power_in"))
      (node (ref "U1") (pin "L15") (pinfunction "VCCINT_L15") (pintype "power_in"))
      (node (ref "U1") (pin "L9") (pinfunction "VCCINT_L9") (pintype "power_in"))
      (node (ref "U1") (pin "M14") (pinfunction "VCCINT_M14") (pintype "power_in"))
      (node (ref "U1") (pin "M8") (pinfunction "VCCINT_M8") (pintype "power_in"))
      (node (ref "U1") (pin "N13") (pinfunction "VCCBRAM_N13") (pintype "power_in"))
      (node (ref "U1") (pin "N15") (pinfunction "VCCINT_N15") (pintype "power_in"))
      (node (ref "U1") (pin "N9") (pinfunction "VCCINT_N9") (pintype "power_in"))
      (node (ref "U1") (pin "P14") (pinfunction "VCCINT_P14") (pintype "power_in"))
      (node (ref "U1") (pin "R13") (pinfunction "VCCBRAM_R13") (pintype "power_in"))
      (node (ref "U1") (pin "R15") (pinfunction "VCCINT_R15") (pintype "power_in"))
      (node (ref "U1") (pin "T12") (pinfunction "VCCBRAM_T12") (pintype "power_in"))
      (node (ref "U1") (pin "T14") (pinfunction "VCCINT_T14") (pintype "power_in"))
      (node (ref "U1") (pin "U13") (pinfunction "VCCBRAM_U13") (pintype "power_in"))
      (node (ref "U1") (pin "U15") (pinfunction "VCCINT_U15") (pintype "power_in"))
    )
    (net (code "7") (name "VCC1V5") (class "Default")
      (node (ref "C212") (pin "1") (pinfunction "1_1") (pintype "passive"))
      (node (ref "C223") (pin "1") (pinfunction "1_1") (pintype "passive"))
      (node (ref "C231") (pin "1") (pinfunction "1_1") (pintype "passive"))
      (node (ref "C245") (pin "1") (pinfunction "1_1") (pintype "passive"))
      (node (ref "C253") (pin "1") (pinfunction "1_1") (pintype "passive"))
      (node (ref "C254") (pin "1") (pinfunction "1_1") (pintype "passive"))
      (node (ref "C271") (pin "1") (pinfunction "1_1") (pintype "passive"))
      (node (ref "C272") (pin "1") (pinfunction "1_1") (pintype "passive"))
      (node (ref "C274") (pin "1") (pinfunction "1_1") (pintype "passive"))
      (node (ref "U1") (pin "AA1") (pinfunction "VCCO_34_AA1") (pintype "power_in"))
      (node (ref "U1") (pin "AA11") (pinfunction "VCCO_33_AA11") (pintype "power_in"))
      (node (ref "U1") (pin "AB18") (pinfunction "VCCO_32_AB18") (pintype "power_in"))
      (node (ref "U1") (pin "AB8") (pinfunction "VCCO_33_AB8") (pintype "power_in"))
      (node (ref "U1") (pin "AC15") (pinfunction "VCCO_32_AC15") (pintype "power_in"))
      (node (ref "U1") (pin "AC5") (pinfunction "VCCO_34_AC5") (pintype "power_in"))
      (node (ref "U1") (pin "AD12") (pinfunction "VCCO_33_AD12") (pintype "power_in"))
      (node (ref "U1") (pin "AD2") (pinfunction "VCCO_34_AD2") (pintype "power_in"))
      (node (ref "U1") (pin "AE19") (pinfunction "VCCO_32_AE19") (pintype "power_in"))
      (node (ref "U1") (pin "AE9") (pinfunction "VCCO_33_AE9") (pintype "power_in"))
      (node (ref "U1") (pin "AF16") (pinfunction "VCCO_32_AF16") (pintype "power_in"))
      (node (ref "U1") (pin "AF6") (pinfunction "VCCO_34_AF6") (pintype "power_in"))
      (node (ref "U1") (pin "U3") (pinfunction "VCCO_34_U3") (pintype "power_in"))
      (node (ref "U1") (pin "V10") (pinfunction "VCCO_33_V10") (pintype "power_in"))
      (node (ref "U1") (pin "W17") (pinfunction "VCCO_32_W17") (pintype "power_in"))
      (node (ref "U1") (pin "W7") (pinfunction "VCCO_33_W7") (pintype "power_in"))
      (node (ref "U1") (pin "Y14") (pinfunction "VCCO_32_Y14") (pintype "power_in"))
      (node (ref "U1") (pin "Y4") (pinfunction "VCCO_34_Y4") (pintype "power_in"))
    )
    (net (code "8") (name "VCC1V8") (class "Default")
      (node (ref "C226") (pin "1") (pinfunction "1_1") (pintype "passive"))
      (node (ref "C227") (pin "1") (pinfunction "1_1") (pintype "passive"))
      (node (ref "C234") (pin "1") (pinfunction "1_1") (pintype "passive"))
      (node (ref "C235") (pin "1") (pinfunction "1_1") (pintype "passive"))
      (node (ref "C236") (pin "1") (pinfunction "1_1") (pintype "passive"))
      (node (ref "C243") (pin "1") (pinfunction "1_1") (pintype "passive"))
      (node (ref "C244") (pin "1") (pinfunction "1_1") (pintype "passive"))
      (node (ref "C249") (pin "1") (pinfunction "1_1") (pintype "passive"))
      (node (ref "U1") (pin "A21") (pinfunction "VCCO_14_A21") (pintype "power_in"))
      (node (ref "U1") (pin "AA21") (pinfunction "VCCO_12_AA21") (pintype "power_in"))
      (node (ref "U1") (pin "AC25") (pinfunction "VCCO_12_AC25") (pintype "power_in"))
      (node (ref "U1") (pin "AD22") (pinfunction "VCCO_12_AD22") (pintype "power_in"))
      (node (ref "U1") (pin "AF26") (pinfunction "VCCO_12_AF26") (pintype "power_in"))
      (node (ref "U1") (pin "C25") (pinfunction "VCCO_14_C25") (pintype "power_in"))
      (node (ref "U1") (pin "D22") (pinfunction "VCCO_14_D22") (pintype "power_in"))
      (node (ref "U1") (pin "F26") (pinfunction "VCCO_14_F26") (pintype "power_in"))
      (node (ref "U1") (pin "G23") (pinfunction "VCCO_14_G23") (pintype "power_in"))
      (node (ref "U1") (pin "L21") (pinfunction "VCCO_14_L21") (pintype "power_in"))
      (node (ref "U1") (pin "L7") (pinfunction "VCCO_0_L7") (pintype "power_in"))
      (node (ref "U1") (pin "T6") (pinfunction "VCCO_0_T6") (pintype "power_in"))
      (node (ref "U1") (pin "U23") (pinfunction "VCCO_12_U23") (pintype "power_in"))
      (node (ref "U1") (pin "V20") (pinfunction "VCCO_12_V20") (pintype "power_in"))
      (node (ref "U1") (pin "Y24") (pinfunction "VCCO_12_Y24") (pintype "power_in"))
    )
    (net (code "9") (name "VCC1V8_AUX") (class "Default")
      (node (ref "C214") (pin "1") (pinfunction "1_1") (pintype "passive"))
      (node (ref "C215") (pin "1") (pinfunction "1_1") (pintype "passive"))
      (node (ref "C216") (pin "1") (pinfunction "1_1") (pintype "passive"))
      (node (ref "C233") (pin "1") (pinfunction "1_1") (pintype "passive"))
      (node (ref "C246") (pin "1") (pinfunction "1_1") (pintype "passive"))
      (node (ref "C269") (pin "1") (pinfunction "1_1") (pintype "passive"))
      (node (ref "C421") (pin "1") (pinfunction "1_1") (pintype "passive"))
      (node (ref "C422") (pin "1") (pinfunction "1_1") (pintype "passive"))
      (node (ref "U1") (pin "L11") (pinfunction "VCCAUX_L11") (pintype "power_in"))
      (node (ref "U1") (pin "M10") (pinfunction "VCCAUX_M10") (pintype "power_in"))
      (node (ref "U1") (pin "N6") (pinfunction "MGTVCCAUX_N6") (pintype "power_in"))
      (node (ref "U1") (pin "P10") (pinfunction "VCCAUX_P10") (pintype "power_in"))
      (node (ref "U1") (pin "P8") (pinfunction "VCCAUX_IO_G0_P8") (pintype "power_in"))
      (node (ref "U1") (pin "R9") (pinfunction "VCCAUX_IO_G0_R9") (pintype "power_in"))
      (node (ref "U1") (pin "T10") (pinfunction "VCCAUX_T10") (pintype "power_in"))
      (node (ref "U1") (pin "T8") (pinfunction "VCCAUX_IO_G0_T8") (pintype "power_in"))
      (node (ref "U1") (pin "U11") (pinfunction "VCCAUX_U11") (pintype "power_in"))
    )
    (net (code "10") (name "VCC3V3") (class "Default")
      (node (ref "C205") (pin "1") (pinfunction "1_1") (pintype "passive"))
      (node (ref "C207") (pin "1") (pinfunction "1_1") (pintype "passive"))
      (node (ref "C208") (pin "1") (pinfunction "1_1") (pintype "passive"))
      (node (ref "C225") (pin "1") (pinfunction "1_1") (pintype "passive"))
      (node (ref "U1") (pin "K24") (pinfunction "VCCO_13_K24") (pintype "power_in"))
      (node (ref "U1") (pin "N25") (pinfunction "VCCO_13_N25") (pintype "power_in"))
      (node (ref "U1") (pin "P22") (pinfunction "VCCO_13_P22") (pintype "power_in"))
      (node (ref "U1") (pin "R19") (pinfunction "VCCO_13_R19") (pintype "power_in"))
      (node (ref "U1") (pin "T16") (pinfunction "VCCO_13_T16") (pintype "power_in"))
      (node (ref "U1") (pin "T26") (pinfunction "VCCO_13_T26") (pintype "power_in"))
    )
    (net (code "11") (name "VCC_CRUVI_ADJ") (class "Default")
      (node (ref "C206") (pin "1") (pinfunction "1_1") (pintype "passive"))
      (node (ref "C217") (pin "1") (pinfunction "1_1") (pintype "passive"))
      (node (ref "C218") (pin "1") (pinfunction "1_1") (pintype "passive"))
      (node (ref "C275") (pin "1") (pinfunction "1_1") (pintype "passive"))
      (node (ref "C277") (pin "1") (pinfunction "1_1") (pintype "passive"))
      (node (ref "U1") (pin "A11") (pinfunction "VCCO_16_A11") (pintype "power_in"))
      (node (ref "U1") (pin "B18") (pinfunction "VCCO_15_B18") (pintype "power_in"))
      (node (ref "U1") (pin "B8") (pinfunction "VCCO_16_B8") (pintype "power_in"))
      (node (ref "U1") (pin "C15") (pinfunction "VCCO_16_C15") (pintype "power_in"))
      (node (ref "U1") (pin "D12") (pinfunction "VCCO_16_D12") (pintype "power_in"))
      (node (ref "U1") (pin "E19") (pinfunction "VCCO_15_E19") (pintype "power_in"))
      (node (ref "U1") (pin "E9") (pinfunction "VCCO_16_E9") (pintype "power_in"))
      (node (ref "U1") (pin "F16") (pinfunction "VCCO_15_F16") (pintype "power_in"))
      (node (ref "U1") (pin "G13") (pinfunction "VCCO_16_G13") (pintype "power_in"))
      (node (ref "U1") (pin "H10") (pinfunction "VCCO_16_H10") (pintype "power_in"))
      (node (ref "U1") (pin "H20") (pinfunction "VCCO_15_H20") (pintype "power_in"))
      (node (ref "U1") (pin "J17") (pinfunction "VCCO_15_J17") (pintype "power_in"))
      (node (ref "U1") (pin "M18") (pinfunction "VCCO_15_M18") (pintype "power_in"))
    )
  )
)
